# MineSwipper_Main_controller.net
KiCad netlist of a schematic drawn in EAGLE
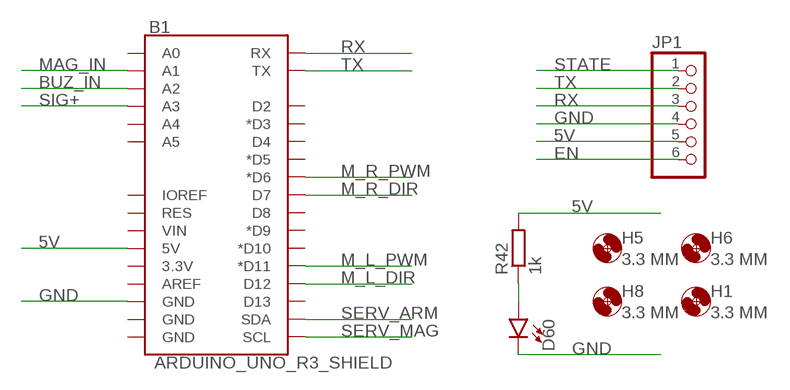
[diagram p0: schematic, sheet 1]
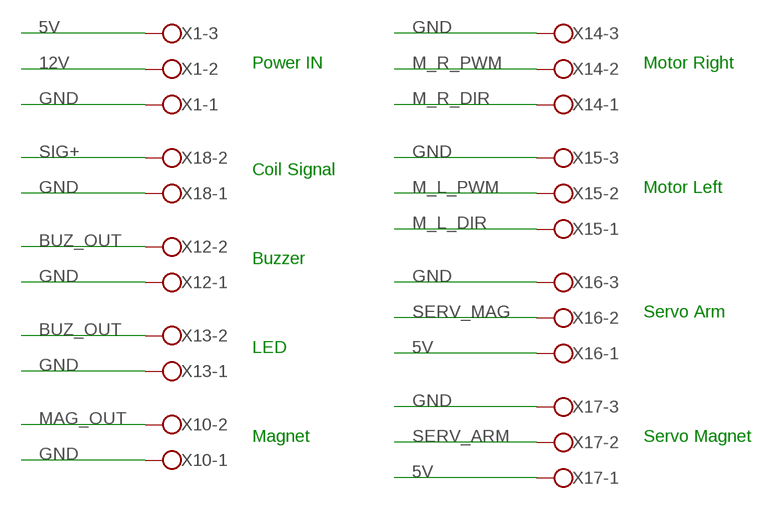
[diagram p1: schematic, sheet 2]
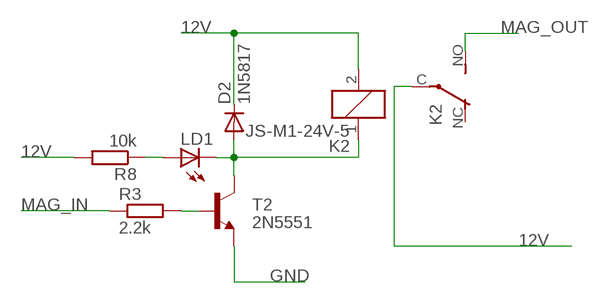
[diagram p2: schematic, sheet 3]
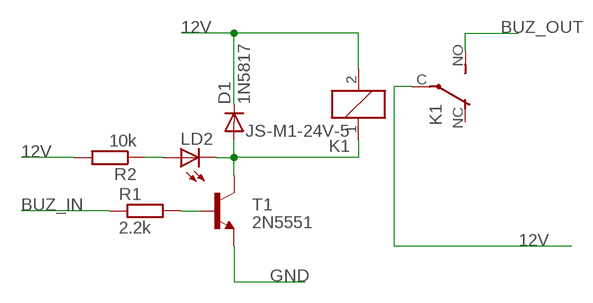
[diagram p3: schematic, sheet 4]

(export (version "E")
  (design (tool "Eeschema 10.0.6"))
  (components
    (comp (ref "B1")
      (value "ARDUINO_UNO_R3_SHIELD")
      (footprint "eagle-import:UNO_R3_SHIELD_NOLABELS_LOCK")
      (libsource (lib "eagle-import") (part "ARDUINO_UNO_R3_SHIELDUNO_R3_SHIELD_NOLABELS_LOCK"))
    )
    (comp (ref "D60")
      (value "LED5MM")
      (footprint "eagle-import:LED_5MM")
      (libsource (lib "eagle-import") (part "LED5MM"))
    )
    (comp (ref "H1")
      (value "3.3 MM")
      (footprint "eagle-import:3,3")
      (libsource (lib "eagle-import") (part "MOUNT-HOLE3.3"))
    )
    (comp (ref "H5")
      (value "3.3 MM")
      (footprint "eagle-import:3,3")
      (libsource (lib "eagle-import") (part "MOUNT-HOLE3.3"))
    )
    (comp (ref "H6")
      (value "3.3 MM")
      (footprint "eagle-import:3,3")
      (libsource (lib "eagle-import") (part "MOUNT-HOLE3.3"))
    )
    (comp (ref "H8")
      (value "3.3 MM")
      (footprint "eagle-import:3,3")
      (libsource (lib "eagle-import") (part "MOUNT-HOLE3.3"))
    )
    (comp (ref "JP1")
      (value "PINHD-1X6")
      (footprint "eagle-import:1X06")
      (libsource (lib "eagle-import") (part "PINHD-1X6"))
    )
    (comp (ref "R42")
      (value "1k")
      (footprint "eagle-import:0207_10")
      (libsource (lib "eagle-import") (part "R-EU_0207/10"))
    )
    (comp (ref "D1")
      (value "1N5817")
      (footprint "eagle-import:DO41-10")
      (libsource (lib "eagle-import") (part "1N4004"))
    )
    (comp (ref "K1")
      (value "JS-M1-24V-5")
      (footprint "eagle-import:JS-M")
      (fields (field (name "MF") "FARNELL") (field (name "MPN") "JSM1-12V-5"))
      (libsource (lib "eagle-import") (part "JS-M1-12V-5"))
    )
    (comp (ref "LD2")
      (value "LED5MM")
      (footprint "eagle-import:LED5MM")
      (libsource (lib "eagle-import") (part "led_LED5MM"))
    )
    (comp (ref "R1")
      (value "2.2k")
      (footprint "eagle-import:0207_10")
      (libsource (lib "eagle-import") (part "rcl-2_R-EU_0207/10"))
    )
    (comp (ref "R2")
      (value "10k")
      (footprint "eagle-import:0207_10")
      (libsource (lib "eagle-import") (part "rcl-2_R-EU_0207/10"))
    )
    (comp (ref "T1")
      (value "2N5551")
      (footprint "eagle-import:TO92-EBC-OVAL")
      (libsource (lib "eagle-import") (part "2N2222"))
    )
    (comp (ref "X1")
      (value "W237-103")
      (footprint "eagle-import:W237-103")
      (fields (field (name "MPN") "237-103"))
      (libsource (lib "eagle-import") (part "W237-103"))
    )
    (comp (ref "X10")
      (value "W237-102")
      (footprint "eagle-import:W237-102")
      (fields (field (name "MPN") "237-102"))
      (libsource (lib "eagle-import") (part "W237-102"))
    )
    (comp (ref "X12")
      (value "W237-102")
      (footprint "eagle-import:W237-102")
      (fields (field (name "MPN") "237-102"))
      (libsource (lib "eagle-import") (part "W237-102"))
    )
    (comp (ref "X13")
      (value "W237-102")
      (footprint "eagle-import:W237-102")
      (fields (field (name "MPN") "237-102"))
      (libsource (lib "eagle-import") (part "W237-102"))
    )
    (comp (ref "X14")
      (value "W237-103")
      (footprint "eagle-import:W237-103")
      (fields (field (name "MPN") "237-103"))
      (libsource (lib "eagle-import") (part "W237-103"))
    )
    (comp (ref "X15")
      (value "W237-103")
      (footprint "eagle-import:W237-103")
      (fields (field (name "MPN") "237-103"))
      (libsource (lib "eagle-import") (part "W237-103"))
    )
    (comp (ref "X16")
      (value "W237-103")
      (footprint "eagle-import:W237-103")
      (fields (field (name "MPN") "237-103"))
      (libsource (lib "eagle-import") (part "W237-103"))
    )
    (comp (ref "X17")
      (value "W237-103")
      (footprint "eagle-import:W237-103")
      (fields (field (name "MPN") "237-103"))
      (libsource (lib "eagle-import") (part "W237-103"))
    )
    (comp (ref "X18")
      (value "W237-102")
      (footprint "eagle-import:W237-102")
      (fields (field (name "MPN") "237-102"))
      (libsource (lib "eagle-import") (part "W237-102"))
    )
    (comp (ref "D2")
      (value "1N5817")
      (footprint "eagle-import:DO41-10")
      (libsource (lib "eagle-import") (part "1N4004"))
    )
    (comp (ref "K2")
      (value "JS-M1-24V-5")
      (footprint "eagle-import:JS-M")
      (fields (field (name "MF") "FARNELL") (field (name "MPN") "JSM1-12V-5"))
      (libsource (lib "eagle-import") (part "JS-M1-12V-5"))
    )
    (comp (ref "LD1")
      (value "LED5MM")
      (footprint "eagle-import:LED5MM")
      (libsource (lib "eagle-import") (part "led_LED5MM"))
    )
    (comp (ref "R3")
      (value "2.2k")
      (footprint "eagle-import:0207_10")
      (libsource (lib "eagle-import") (part "rcl-2_R-EU_0207/10"))
    )
    (comp (ref "R8")
      (value "10k")
      (footprint "eagle-import:0207_10")
      (libsource (lib "eagle-import") (part "rcl-2_R-EU_0207/10"))
    )
    (comp (ref "T2")
      (value "2N5551")
      (footprint "eagle-import:TO92-EBC-OVAL")
      (libsource (lib "eagle-import") (part "2N2222"))
    )
  )
  (nets
    (net (code "1") (name "5V") (class "Default")
      (node (ref "B1") (pin "5V") (pinfunction "5V_5V") (pintype "bidirectional"))
      (node (ref "JP1") (pin "5") (pinfunction "5_5") (pintype "passive"))
      (node (ref "R42") (pin "2") (pinfunction "2_2") (pintype "passive"))
      (node (ref "X1") (pin "3") (pinfunction "KL_3") (pintype "passive"))
      (node (ref "X16") (pin "1") (pinfunction "KL_1") (pintype "passive"))
      (node (ref "X17") (pin "1") (pinfunction "KL_1") (pintype "passive"))
    )
    (net (code "2") (name "12V") (class "Default")
      (node (ref "D1") (pin "C") (pinfunction "C_C") (pintype "passive"))
      (node (ref "D2") (pin "C") (pinfunction "C_C") (pintype "passive"))
      (node (ref "K1") (pin "2") (pinfunction "2_2") (pintype "passive"))
      (node (ref "K1") (pin "C") (pinfunction "P_C") (pintype "passive"))
      (node (ref "K2") (pin "2") (pinfunction "2_2") (pintype "passive"))
      (node (ref "K2") (pin "C") (pinfunction "P_C") (pintype "passive"))
      (node (ref "R2") (pin "2") (pinfunction "2_2") (pintype "passive"))
      (node (ref "R8") (pin "2") (pinfunction "2_2") (pintype "passive"))
      (node (ref "X1") (pin "2") (pinfunction "KL_2") (pintype "passive"))
    )
    (net (code "3") (name "BUZ_IN") (class "Default")
      (node (ref "B1") (pin "A2") (pinfunction "A2_A2") (pintype "bidirectional"))
      (node (ref "R1") (pin "1") (pinfunction "1_1") (pintype "passive"))
    )
    (net (code "4") (name "BUZ_OUT") (class "Default")
      (node (ref "K1") (pin "NO") (pinfunction "S_NO") (pintype "passive"))
      (node (ref "X12") (pin "2") (pinfunction "KL_2") (pintype "passive"))
      (node (ref "X13") (pin "2") (pinfunction "KL_2") (pintype "passive"))
    )
    (net (code "5") (name "EN") (class "Default")
      (node (ref "JP1") (pin "6") (pinfunction "6_6") (pintype "passive"))
    )
    (net (code "6") (name "GND") (class "Default")
      (node (ref "B1") (pin "GND@2") (pinfunction "GND_GND@2") (pintype "bidirectional"))
      (node (ref "D60") (pin "K") (pinfunction "C_K") (pintype "passive"))
      (node (ref "JP1") (pin "4") (pinfunction "4_4") (pintype "passive"))
      (node (ref "T1") (pin "E") (pinfunction "E_E") (pintype "passive"))
      (node (ref "T2") (pin "E") (pinfunction "E_E") (pintype "passive"))
      (node (ref "X1") (pin "1") (pinfunction "KL_1") (pintype "passive"))
      (node (ref "X10") (pin "1") (pinfunction "KL_1") (pintype "passive"))
      (node (ref "X12") (pin "1") (pinfunction "KL_1") (pintype "passive"))
      (node (ref "X13") (pin "1") (pinfunction "KL_1") (pintype "passive"))
      (node (ref "X14") (pin "3") (pinfunction "KL_3") (pintype "passive"))
      (node (ref "X15") (pin "3") (pinfunction "KL_3") (pintype "passive"))
      (node (ref "X16") (pin "3") (pinfunction "KL_3") (pintype "passive"))
      (node (ref "X17") (pin "3") (pinfunction "KL_3") (pintype "passive"))
      (node (ref "X18") (pin "1") (pinfunction "KL_1") (pintype "passive"))
    )
    (net (code "7") (name "MAG_IN") (class "Default")
      (node (ref "B1") (pin "A1") (pinfunction "A1_A1") (pintype "bidirectional"))
      (node (ref "R3") (pin "1") (pinfunction "1_1") (pintype "passive"))
    )
    (net (code "8") (name "MAG_OUT") (class "Default")
      (node (ref "K2") (pin "NO") (pinfunction "S_NO") (pintype "passive"))
      (node (ref "X10") (pin "2") (pinfunction "KL_2") (pintype "passive"))
    )
    (net (code "9") (name "M_L_DIR") (class "Default")
      (node (ref "B1") (pin "D12") (pinfunction "D12_D12") (pintype "bidirectional"))
      (node (ref "X15") (pin "1") (pinfunction "KL_1") (pintype "passive"))
    )
    (net (code "10") (name "M_L_PWM") (class "Default")
      (node (ref "B1") (pin "D11") (pinfunction "*D11_D11") (pintype "bidirectional"))
      (node (ref "X15") (pin "2") (pinfunction "KL_2") (pintype "passive"))
    )
    (net (code "11") (name "M_R_DIR") (class "Default")
      (node (ref "B1") (pin "D7") (pinfunction "D7_D7") (pintype "bidirectional"))
      (node (ref "X14") (pin "1") (pinfunction "KL_1") (pintype "passive"))
    )
    (net (code "12") (name "M_R_PWM") (class "Default")
      (node (ref "B1") (pin "D6") (pinfunction "*D6_D6") (pintype "bidirectional"))
      (node (ref "X14") (pin "2") (pinfunction "KL_2") (pintype "passive"))
    )
    (net (code "13") (name "Net-(D60-PadA)") (class "Default")
      (node (ref "D60") (pin "A") (pinfunction "A_A") (pintype "passive"))
      (node (ref "R42") (pin "1") (pinfunction "1_1") (pintype "passive"))
    )
    (net (code "14") (name "Net-(LD1-C)") (class "Default")
      (node (ref "D2") (pin "A") (pinfunction "A_A") (pintype "passive"))
      (node (ref "K2") (pin "1") (pinfunction "1_1") (pintype "passive"))
      (node (ref "LD1") (pin "K") (pinfunction "C_K") (pintype "passive"))
      (node (ref "T2") (pin "C") (pinfunction "C_C") (pintype "passive"))
    )
    (net (code "15") (name "Net-(LD1-PadA)") (class "Default")
      (node (ref "LD1") (pin "A") (pinfunction "A_A") (pintype "passive"))
      (node (ref "R8") (pin "1") (pinfunction "1_1") (pintype "passive"))
    )
    (net (code "16") (name "Net-(LD2-C)") (class "Default")
      (node (ref "D1") (pin "A") (pinfunction "A_A") (pintype "passive"))
      (node (ref "K1") (pin "1") (pinfunction "1_1") (pintype "passive"))
      (node (ref "LD2") (pin "K") (pinfunction "C_K") (pintype "passive"))
      (node (ref "T1") (pin "C") (pinfunction "C_C") (pintype "passive"))
    )
    (net (code "17") (name "Net-(LD2-PadA)") (class "Default")
      (node (ref "LD2") (pin "A") (pinfunction "A_A") (pintype "passive"))
      (node (ref "R2") (pin "1") (pinfunction "1_1") (pintype "passive"))
    )
    (net (code "18") (name "Net-(R1-Pad2)") (class "Default")
      (node (ref "R1") (pin "2") (pinfunction "2_2") (pintype "passive"))
      (node (ref "T1") (pin "B") (pinfunction "B_B") (pintype "passive"))
    )
    (net (code "19") (name "Net-(R3-Pad2)") (class "Default")
      (node (ref "R3") (pin "2") (pinfunction "2_2") (pintype "passive"))
      (node (ref "T2") (pin "B") (pinfunction "B_B") (pintype "passive"))
    )
    (net (code "20") (name "RX") (class "Default")
      (node (ref "B1") (pin "RX") (pinfunction "RX_RX") (pintype "bidirectional"))
      (node (ref "JP1") (pin "3") (pinfunction "3_3") (pintype "passive"))
    )
    (net (code "21") (name "SERV_ARM") (class "Default")
      (node (ref "B1") (pin "SDA") (pinfunction "SDA_SDA") (pintype "bidirectional"))
      (node (ref "X17") (pin "2") (pinfunction "KL_2") (pintype "passive"))
    )
    (net (code "22") (name "SERV_MAG") (class "Default")
      (node (ref "B1") (pin "SCL") (pinfunction "SCL_SCL") (pintype "bidirectional"))
      (node (ref "X16") (pin "2") (pinfunction "KL_2") (pintype "passive"))
    )
    (net (code "23") (name "SIG+") (class "Default")
      (node (ref "B1") (pin "A3") (pinfunction "A3_A3") (pintype "bidirectional"))
      (node (ref "X18") (pin "2") (pinfunction "KL_2") (pintype "passive"))
    )
    (net (code "24") (name "STATE") (class "Default")
      (node (ref "JP1") (pin "1") (pinfunction "1_1") (pintype "passive"))
    )
    (net (code "25") (name "TX") (class "Default")
      (node (ref "B1") (pin "TX") (pinfunction "TX_TX") (pintype "bidirectional"))
      (node (ref "JP1") (pin "2") (pinfunction "2_2") (pintype "passive"))
    )
    (net (code "26") (name "unconnected-(B1-*D3-PadD3)") (class "Default")
      (node (ref "B1") (pin "D3") (pinfunction "*D3_D3") (pintype "bidirectional"))
    )
    (net (code "27") (name "unconnected-(B1-*D5-PadD5)") (class "Default")
      (node (ref "B1") (pin "D5") (pinfunction "*D5_D5") (pintype "bidirectional"))
    )
    (net (code "28") (name "unconnected-(B1-*D9-PadD9)") (class "Default")
      (node (ref "B1") (pin "D9") (pinfunction "*D9_D9") (pintype "bidirectional"))
    )
    (net (code "29") (name "unconnected-(B1-*D10-PadD10)") (class "Default")
      (node (ref "B1") (pin "D10") (pinfunction "*D10_D10") (pintype "bidirectional"))
    )
    (net (code "30") (name "unconnected-(B1-GND-PadGND@0)") (class "Default")
      (node (ref "B1") (pin "GND@0") (pinfunction "GND_GND@0") (pintype "bidirectional"))
    )
    (net (code "31") (name "unconnected-(B1-GND-PadGND@1)") (class "Default")
      (node (ref "B1") (pin "GND@1") (pinfunction "GND_GND@1") (pintype "bidirectional"))
    )
    (net (code "32") (name "unconnected-(B1-Pad3.3V)") (class "Default")
      (node (ref "B1") (pin "3.3V") (pinfunction "3.3V_3.3V") (pintype "bidirectional"))
    )
    (net (code "33") (name "unconnected-(B1-PadA0)") (class "Default")
      (node (ref "B1") (pin "A0") (pinfunction "A0_A0") (pintype "bidirectional"))
    )
    (net (code "34") (name "unconnected-(B1-PadA4)") (class "Default")
      (node (ref "B1") (pin "A4") (pinfunction "A4_A4") (pintype "bidirectional"))
    )
    (net (code "35") (name "unconnected-(B1-PadA5)") (class "Default")
      (node (ref "B1") (pin "A5") (pinfunction "A5_A5") (pintype "bidirectional"))
    )
    (net (code "36") (name "unconnected-(B1-PadAREF)") (class "Default")
      (node (ref "B1") (pin "AREF") (pinfunction "AREF_AREF") (pintype "bidirectional"))
    )
    (net (code "37") (name "unconnected-(B1-PadD2)") (class "Default")
      (node (ref "B1") (pin "D2") (pinfunction "D2_D2") (pintype "bidirectional"))
    )
    (net (code "38") (name "unconnected-(B1-PadD4)") (class "Default")
      (node (ref "B1") (pin "D4") (pinfunction "D4_D4") (pintype "bidirectional"))
    )
    (net (code "39") (name "unconnected-(B1-PadD8)") (class "Default")
      (node (ref "B1") (pin "D8") (pinfunction "D8_D8") (pintype "bidirectional"))
    )
    (net (code "40") (name "unconnected-(B1-PadD13)") (class "Default")
      (node (ref "B1") (pin "D13") (pinfunction "D13_D13") (pintype "bidirectional"))
    )
    (net (code "41") (name "unconnected-(B1-PadIOREF)") (class "Default")
      (node (ref "B1") (pin "IOREF") (pinfunction "IOREF_IOREF") (pintype "bidirectional"))
    )
    (net (code "42") (name "unconnected-(B1-PadRES)") (class "Default")
      (node (ref "B1") (pin "RES") (pinfunction "RES_RES") (pintype "bidirectional"))
    )
    (net (code "43") (name "unconnected-(B1-PadVIN)") (class "Default")
      (node (ref "B1") (pin "VIN") (pinfunction "VIN_VIN") (pintype "bidirectional"))
    )
    (net (code "44") (name "unconnected-(K1B-O-PadNC)") (class "Default")
      (node (ref "K1") (pin "NC") (pinfunction "O_NC") (pintype "passive"))
    )
    (net (code "45") (name "unconnected-(K2B-O-PadNC)") (class "Default")
      (node (ref "K2") (pin "NC") (pinfunction "O_NC") (pintype "passive"))
    )
  )
)
